# pic1.net
KiCad netlist of a schematic drawn in EAGLE
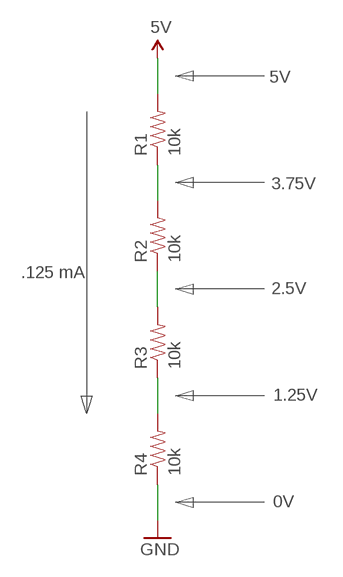
[diagram p0: schematic, sheet 1]

(export (version "E")
  (design (tool "Eeschema 10.0.6"))
  (components
    (comp (ref "R1")
      (value "10k")
      (footprint "eagle-import:0603-RES")
      (fields (field (name "PROD_ID") "RES-00818"))
      (libsource (lib "eagle-import") (part "330OHM1/10W1%(0603)"))
    )
    (comp (ref "R2")
      (value "10k")
      (footprint "eagle-import:0603-RES")
      (fields (field (name "PROD_ID") "RES-00818"))
      (libsource (lib "eagle-import") (part "330OHM1/10W1%(0603)"))
    )
    (comp (ref "R3")
      (value "10k")
      (footprint "eagle-import:0603-RES")
      (fields (field (name "PROD_ID") "RES-00818"))
      (libsource (lib "eagle-import") (part "330OHM1/10W1%(0603)"))
    )
    (comp (ref "R4")
      (value "10k")
      (footprint "eagle-import:0603-RES")
      (fields (field (name "PROD_ID") "RES-00818"))
      (libsource (lib "eagle-import") (part "330OHM1/10W1%(0603)"))
    )
  )
  (nets
    (net (code "1") (name "5V") (class "Default")
      (node (ref "R1") (pin "2") (pinfunction "2_2") (pintype "passive"))
    )
    (net (code "2") (name "GND") (class "Default")
      (node (ref "R4") (pin "1") (pinfunction "1_1") (pintype "passive"))
    )
    (net (code "3") (name "Net-(R1-Pad1)") (class "Default")
      (node (ref "R1") (pin "1") (pinfunction "1_1") (pintype "passive"))
      (node (ref "R2") (pin "2") (pinfunction "2_2") (pintype "passive"))
    )
    (net (code "4") (name "Net-(R2-Pad1)") (class "Default")
      (node (ref "R2") (pin "1") (pinfunction "1_1") (pintype "passive"))
      (node (ref "R3") (pin "2") (pinfunction "2_2") (pintype "passive"))
    )
    (net (code "5") (name "Net-(R3-Pad1)") (class "Default")
      (node (ref "R3") (pin "1") (pinfunction "1_1") (pintype "passive"))
      (node (ref "R4") (pin "2") (pinfunction "2_2") (pintype "passive"))
    )
  )
)
